# schematic.net
KiCad netlist of a schematic drawn in Altium Designer
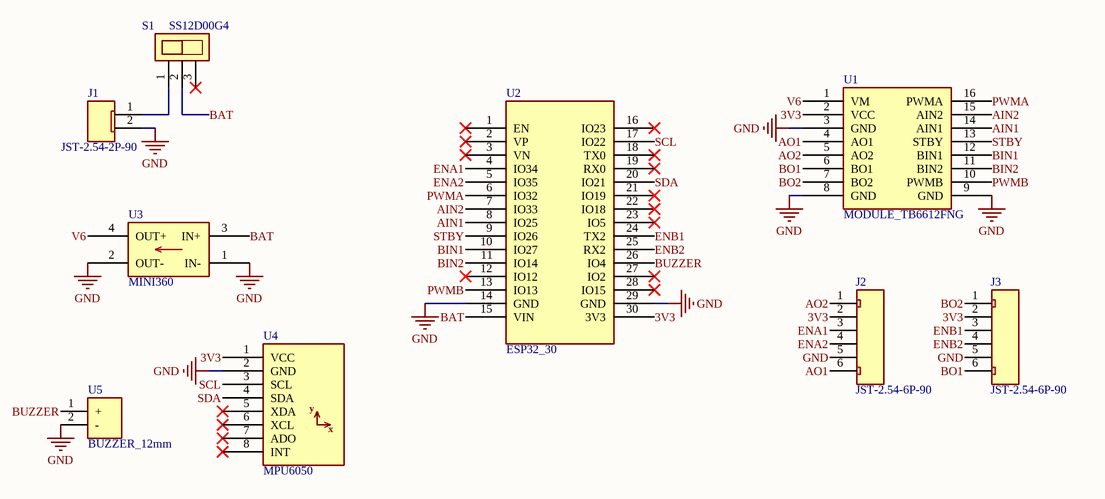
[diagram p0: schematic.SchDoc]

(export (version "E")
  (design (tool "Eeschema 10.0.6"))
  (components
    (comp (ref "J1")
      (value "JST-2.54-2P-90")
      (footprint "JST-2.54-2P-90")
      (description "Female Connector JST 2 Vias, 2.54mm 90º.")
      (libsource (lib "Connectors") (part "JST-2.54-2P-90"))
    )
    (comp (ref "J2")
      (value "JST-2.54-6P-90")
      (footprint "JST-2.54-6P-90")
      (description "Female Connector JST 6 Vias, 2.54mm 90º.")
      (libsource (lib "Connectors") (part "JST-2.54-6P-90"))
    )
    (comp (ref "J3")
      (value "JST-2.54-6P-90")
      (footprint "JST-2.54-6P-90")
      (description "Female Connector JST 6 Vias, 2.54mm 90º.")
      (libsource (lib "Connectors") (part "JST-2.54-6P-90"))
    )
    (comp (ref "S1")
      (value "SS12D00G4")
      (footprint "SS12D00G4")
      (libsource (lib "Buttons & Switches") (part "SS12D00G4"))
    )
    (comp (ref "U1")
      (value "MODULE_TB6612FNG")
      (footprint "MODULE_TB6612FNG")
      (description "Module Dual Motor Driver 2.5-13.5V 3.2A Peak 21x18mm")
      (libsource (lib "Motor Drivers") (part "MODULE_TB6612FNG"))
    )
    (comp (ref "U2")
      (value "ESP32_30")
      (footprint "ESP32_30")
      (description "Microcontoller Board 30 Pins Wifi 2.4GHz BLE 4.2 ESP32-WROOM-32D")
      (libsource (lib "Espressif Microcontrollers") (part "ESP32_30"))
    )
    (comp (ref "U3")
      (value "MINI360")
      (footprint "MINI360")
      (description "MODULE BUCK STEP DOWN 3A 18x12mm")
      (libsource (lib "Voltage Regulators") (part "MINI360"))
    )
    (comp (ref "U4")
      (value "MPU6050")
      (footprint "MPU6050")
      (description "IMU ACCEL/GYRO 3-AXIS I2C")
      (libsource (lib "Sensors") (part "MPU6050"))
    )
    (comp (ref "U5")
      (value "BUZZER_12mm")
      (footprint "BUZZER_12mm")
      (description "BUZZER MAGNETIC 12MM")
      (libsource (lib "Random") (part "BUZZER_12mm"))
    )
  )
  (nets
    (net (code "1") (name "/3V3") (class "Default")
      (node (ref "J2") (pin "2") (pintype "passive"))
      (node (ref "J3") (pin "2") (pintype "passive"))
      (node (ref "U1") (pin "2") (pinfunction "VCC_2") (pintype "passive"))
      (node (ref "U2") (pin "30") (pinfunction "3V3_30") (pintype "passive"))
      (node (ref "U4") (pin "1") (pinfunction "VCC_1") (pintype "passive"))
    )
    (net (code "2") (name "/AIN1") (class "Default")
      (node (ref "U1") (pin "14") (pinfunction "AIN1_14") (pintype "passive"))
      (node (ref "U2") (pin "8") (pinfunction "IO25_8") (pintype "passive"))
    )
    (net (code "3") (name "/AIN2") (class "Default")
      (node (ref "U1") (pin "15") (pinfunction "AIN2_15") (pintype "passive"))
      (node (ref "U2") (pin "7") (pinfunction "IO33_7") (pintype "passive"))
    )
    (net (code "4") (name "/AO1") (class "Default")
      (node (ref "J2") (pin "6") (pintype "passive"))
      (node (ref "U1") (pin "4") (pinfunction "AO1_4") (pintype "passive"))
    )
    (net (code "5") (name "/AO2") (class "Default")
      (node (ref "J2") (pin "1") (pintype "passive"))
      (node (ref "U1") (pin "5") (pinfunction "AO2_5") (pintype "passive"))
    )
    (net (code "6") (name "/BAT") (class "Default")
      (node (ref "S1") (pin "2") (pintype "passive"))
      (node (ref "U2") (pin "15") (pinfunction "VIN_15") (pintype "passive"))
      (node (ref "U3") (pin "3") (pinfunction "IN+_3") (pintype "passive"))
    )
    (net (code "7") (name "/BIN1") (class "Default")
      (node (ref "U1") (pin "12") (pinfunction "BIN1_12") (pintype "passive"))
      (node (ref "U2") (pin "10") (pinfunction "IO27_10") (pintype "passive"))
    )
    (net (code "8") (name "/BIN2") (class "Default")
      (node (ref "U1") (pin "11") (pinfunction "BIN2_11") (pintype "passive"))
      (node (ref "U2") (pin "11") (pinfunction "IO14_11") (pintype "passive"))
    )
    (net (code "9") (name "/BO1") (class "Default")
      (node (ref "J3") (pin "6") (pintype "passive"))
      (node (ref "U1") (pin "6") (pinfunction "BO1_6") (pintype "passive"))
    )
    (net (code "10") (name "/BO2") (class "Default")
      (node (ref "J3") (pin "1") (pintype "passive"))
      (node (ref "U1") (pin "7") (pinfunction "BO2_7") (pintype "passive"))
    )
    (net (code "11") (name "/BUZZER") (class "Default")
      (node (ref "U2") (pin "26") (pinfunction "IO4_26") (pintype "passive"))
      (node (ref "U5") (pin "1") (pinfunction "+_1") (pintype "passive"))
    )
    (net (code "12") (name "/ENA1") (class "Default")
      (node (ref "J2") (pin "3") (pintype "passive"))
      (node (ref "U2") (pin "4") (pinfunction "IO34_4") (pintype "passive"))
    )
    (net (code "13") (name "/ENA2") (class "Default")
      (node (ref "J2") (pin "4") (pintype "passive"))
      (node (ref "U2") (pin "5") (pinfunction "IO35_5") (pintype "passive"))
    )
    (net (code "14") (name "/ENB1") (class "Default")
      (node (ref "J3") (pin "3") (pintype "passive"))
      (node (ref "U2") (pin "24") (pinfunction "TX2_24") (pintype "passive"))
    )
    (net (code "15") (name "/ENB2") (class "Default")
      (node (ref "J3") (pin "4") (pintype "passive"))
      (node (ref "U2") (pin "25") (pinfunction "RX2_25") (pintype "passive"))
    )
    (net (code "16") (name "/PWMA") (class "Default")
      (node (ref "U1") (pin "16") (pinfunction "PWMA_16") (pintype "passive"))
      (node (ref "U2") (pin "6") (pinfunction "IO32_6") (pintype "passive"))
    )
    (net (code "17") (name "/PWMB") (class "Default")
      (node (ref "U1") (pin "10") (pinfunction "PWMB_10") (pintype "passive"))
      (node (ref "U2") (pin "13") (pinfunction "IO13_13") (pintype "passive"))
    )
    (net (code "18") (name "/SCL") (class "Default")
      (node (ref "U2") (pin "17") (pinfunction "IO22_17") (pintype "passive"))
      (node (ref "U4") (pin "3") (pinfunction "SCL_3") (pintype "passive"))
    )
    (net (code "19") (name "/SDA") (class "Default")
      (node (ref "U2") (pin "20") (pinfunction "IO21_20") (pintype "passive"))
      (node (ref "U4") (pin "4") (pinfunction "SDA_4") (pintype "passive"))
    )
    (net (code "20") (name "/STBY") (class "Default")
      (node (ref "U1") (pin "13") (pinfunction "STBY_13") (pintype "passive"))
      (node (ref "U2") (pin "9") (pinfunction "IO26_9") (pintype "passive"))
    )
    (net (code "21") (name "/V6") (class "Default")
      (node (ref "U1") (pin "1") (pinfunction "VM_1") (pintype "passive"))
      (node (ref "U3") (pin "4") (pinfunction "OUT+_4") (pintype "passive"))
    )
    (net (code "22") (name "GND") (class "Default")
      (node (ref "J1") (pin "2") (pintype "passive"))
      (node (ref "J2") (pin "5") (pintype "passive"))
      (node (ref "J3") (pin "5") (pintype "passive"))
      (node (ref "U1") (pin "3") (pinfunction "GND_3") (pintype "passive"))
      (node (ref "U1") (pin "8") (pinfunction "GND_8") (pintype "passive"))
      (node (ref "U1") (pin "9") (pinfunction "GND_9") (pintype "passive"))
      (node (ref "U2") (pin "14") (pinfunction "GND_14") (pintype "passive"))
      (node (ref "U2") (pin "29") (pinfunction "GND_29") (pintype "passive"))
      (node (ref "U3") (pin "1") (pinfunction "IN-_1") (pintype "passive"))
      (node (ref "U3") (pin "2") (pinfunction "OUT-_2") (pintype "passive"))
      (node (ref "U4") (pin "2") (pinfunction "GND_2") (pintype "passive"))
      (node (ref "U5") (pin "2") (pinfunction "-_2") (pintype "passive"))
    )
    (net (code "23") (name "Net-(J1-Pad1)") (class "Default")
      (node (ref "J1") (pin "1") (pintype "passive"))
      (node (ref "S1") (pin "1") (pintype "passive"))
    )
    (net (code "24") (name "unconnected-(S1-Pad3)") (class "Default")
      (node (ref "S1") (pin "3") (pintype "passive+no_connect"))
    )
    (net (code "25") (name "unconnected-(U2-EN-Pad1)") (class "Default")
      (node (ref "U2") (pin "1") (pinfunction "EN_1") (pintype "passive+no_connect"))
    )
    (net (code "26") (name "unconnected-(U2-IO2-Pad27)") (class "Default")
      (node (ref "U2") (pin "27") (pinfunction "IO2_27") (pintype "passive+no_connect"))
    )
    (net (code "27") (name "unconnected-(U2-IO5-Pad23)") (class "Default")
      (node (ref "U2") (pin "23") (pinfunction "IO5_23") (pintype "passive+no_connect"))
    )
    (net (code "28") (name "unconnected-(U2-IO12-Pad12)") (class "Default")
      (node (ref "U2") (pin "12") (pinfunction "IO12_12") (pintype "passive+no_connect"))
    )
    (net (code "29") (name "unconnected-(U2-IO15-Pad28)") (class "Default")
      (node (ref "U2") (pin "28") (pinfunction "IO15_28") (pintype "passive+no_connect"))
    )
    (net (code "30") (name "unconnected-(U2-IO18-Pad22)") (class "Default")
      (node (ref "U2") (pin "22") (pinfunction "IO18_22") (pintype "passive+no_connect"))
    )
    (net (code "31") (name "unconnected-(U2-IO19-Pad21)") (class "Default")
      (node (ref "U2") (pin "21") (pinfunction "IO19_21") (pintype "passive+no_connect"))
    )
    (net (code "32") (name "unconnected-(U2-IO23-Pad16)") (class "Default")
      (node (ref "U2") (pin "16") (pinfunction "IO23_16") (pintype "passive+no_connect"))
    )
    (net (code "33") (name "unconnected-(U2-RX0-Pad19)") (class "Default")
      (node (ref "U2") (pin "19") (pinfunction "RX0_19") (pintype "passive+no_connect"))
    )
    (net (code "34") (name "unconnected-(U2-TX0-Pad18)") (class "Default")
      (node (ref "U2") (pin "18") (pinfunction "TX0_18") (pintype "passive+no_connect"))
    )
    (net (code "35") (name "unconnected-(U2-VN-Pad3)") (class "Default")
      (node (ref "U2") (pin "3") (pinfunction "VN_3") (pintype "passive+no_connect"))
    )
    (net (code "36") (name "unconnected-(U2-VP-Pad2)") (class "Default")
      (node (ref "U2") (pin "2") (pinfunction "VP_2") (pintype "passive+no_connect"))
    )
    (net (code "37") (name "unconnected-(U4-ADO-Pad7)") (class "Default")
      (node (ref "U4") (pin "7") (pinfunction "ADO_7") (pintype "passive+no_connect"))
    )
    (net (code "38") (name "unconnected-(U4-INT-Pad8)") (class "Default")
      (node (ref "U4") (pin "8") (pinfunction "INT_8") (pintype "passive+no_connect"))
    )
    (net (code "39") (name "unconnected-(U4-XCL-Pad6)") (class "Default")
      (node (ref "U4") (pin "6") (pinfunction "XCL_6") (pintype "passive+no_connect"))
    )
    (net (code "40") (name "unconnected-(U4-XDA-Pad5)") (class "Default")
      (node (ref "U4") (pin "5") (pinfunction "XDA_5") (pintype "passive+no_connect"))
    )
  )
)
